# Sheet1.net
KiCad netlist of a schematic drawn in Altium Designer
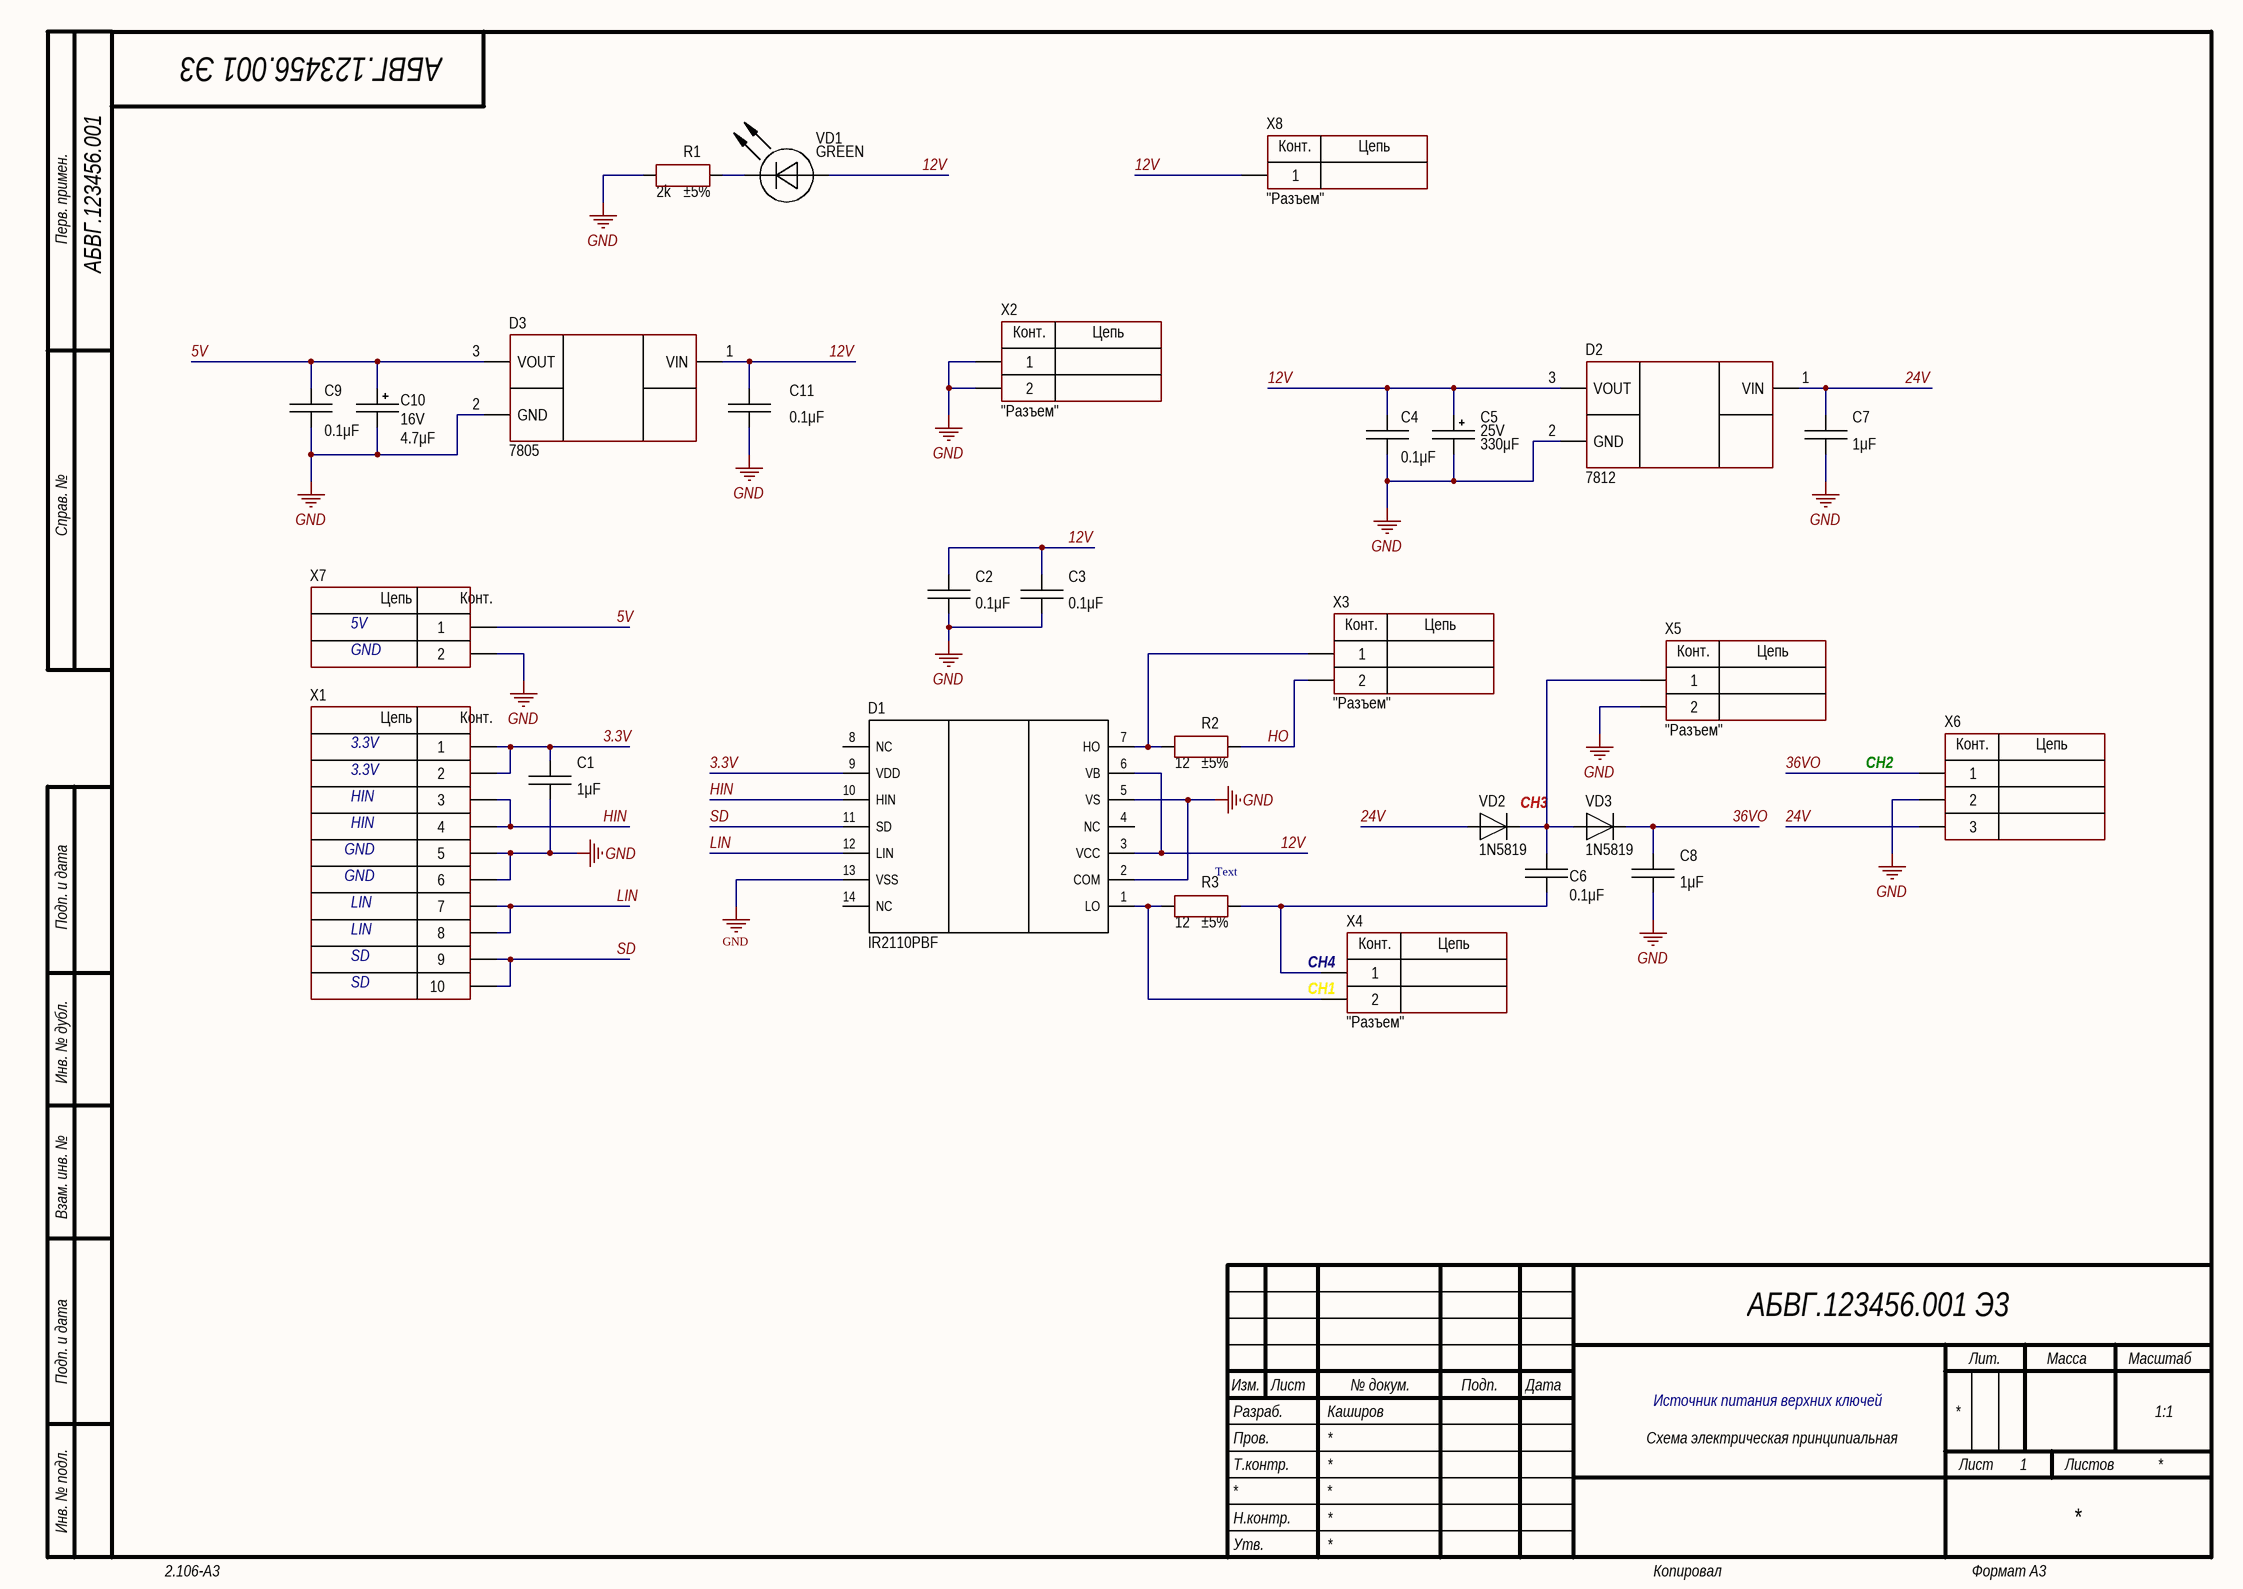
[diagram p0: Sheet1.SchDoc]

(export (version "E")
  (design (tool "Eeschema 10.0.6"))
  (components
    (comp (ref "C1") (value "1μF") (footprint "CAP: HOLE 5mm") (libsource (lib "capacitor") (part "Ceramic")))
    (comp (ref "C2")
      (value "0.1μF")
      (footprint "CAP: 0805")
      (fields
        (field (name "MANUFACTURER") "Yageo")
        (field (name "PARTNUMBER") "CC0805KRX7R7BB104")
        (field (name "VALUEMANUFACTURERPARTNUMBER") "Ceramic capacitor, 0.1μF, X7R, ±10%, , 0805, -55...+125°C")
      )
      (libsource (lib "capacitor") (part "Ceramic_0805"))
    )
    (comp (ref "C3")
      (value "0.1μF")
      (footprint "CAP: 0805")
      (fields
        (field (name "MANUFACTURER") "Yageo")
        (field (name "PARTNUMBER") "CC0805KRX7R7BB104")
        (field (name "VALUEMANUFACTURERPARTNUMBER") "Ceramic capacitor, 0.1μF, X7R, ±10%, , 0805, -55...+125°C")
      )
      (libsource (lib "capacitor") (part "Ceramic_0805"))
    )
    (comp (ref "C4")
      (value "0.1μF")
      (footprint "CAP: HOLE 5mm")
      (libsource (lib "capacitor") (part "Ceramic"))
    )
    (comp (ref "C5")
      (value "330μF")
      (footprint "CAP: D6.3C2.5H11")
      (fields
        (field (name "MANUFACTURER") "Wurth")
        (field (name "PARTNUMBER") "860080475013")
        (field (name "VALUEMANUFACTURERPARTNUMBER") "Aluminium capacitor, 330μF, 25V, ±20%, 54mOhm, 14x10x5 mm, -55...+105°C")
        (field (name "VOLTAGE") "25V")
      )
      (libsource (lib "capacitor") (part "Aluminium"))
    )
    (comp (ref "C6")
      (value "0.1μF")
      (footprint "CAP: HOLE 5mm")
      (libsource (lib "capacitor") (part "Ceramic"))
    )
    (comp (ref "C7") (value "1μF") (footprint "CAP: HOLE 5mm") (libsource (lib "capacitor") (part "Ceramic")))
    (comp (ref "C8") (value "1μF") (footprint "CAP: HOLE 5mm") (libsource (lib "capacitor") (part "Ceramic")))
    (comp (ref "C9")
      (value "0.1μF")
      (footprint "CAP: HOLE 5mm")
      (libsource (lib "capacitor") (part "Ceramic"))
    )
    (comp (ref "C10")
      (value "4.7μF")
      (footprint "CAP: TANTAL-A")
      (fields
        (field (name "MANUFACTURER") "AVX")
        (field (name "PARTNUMBER") "F930J107KAAAJ6")
        (field (name "VALUEMANUFACTURERPARTNUMBER") "Tantalum capacitor, 4.7μF, 16V, ±10%, 2Ohm, case A (3216), -55...+125°C")
        (field (name "VOLTAGE") "16V")
      )
      (libsource (lib "capacitor") (part "Tantal_A"))
    )
    (comp (ref "C11")
      (value "0.1μF")
      (footprint "CAP: 0805")
      (fields
        (field (name "MANUFACTURER") "Yageo")
        (field (name "PARTNUMBER") "CC0805KRX7R7BB104")
        (field (name "VALUEMANUFACTURERPARTNUMBER") "Ceramic capacitor, 0.1μF, X7R, ±10%, , 0805, -55...+125°C")
      )
      (libsource (lib "capacitor") (part "Ceramic_0805"))
    )
    (comp (ref "D1")
      (value "Infineon Technologies")
      (footprint "14-DIP")
      (description "Gate driver")
      (fields (field (name "PARTNUMBER") "IR2110PBF"))
      (libsource (lib "ic-gate-driver") (part "IR2110PBF"))
    )
    (comp (ref "D2")
      (value "*")
      (footprint "TO-220F")
      (description "Linear voltage regulator")
      (fields (field (name "PARTNUMBER") "7812"))
      (libsource (lib "ic-power-supply") (part "78XX"))
    )
    (comp (ref "D3")
      (value "*")
      (footprint "TO-220F")
      (description "Linear voltage regulator")
      (fields (field (name "PARTNUMBER") "7805"))
      (libsource (lib "ic-power-supply") (part "78XX"))
    )
    (comp (ref "R1")
      (value "2k")
      (footprint "RES: Axial 10mm")
      (fields (field (name "TOLERANCE") "±5%"))
      (libsource (lib "resistor") (part "Resistor_Axial"))
    )
    (comp (ref "R2")
      (value "12")
      (footprint "RES: Axial 10mm")
      (fields (field (name "TOLERANCE") "±5%"))
      (libsource (lib "resistor") (part "Resistor_Axial"))
    )
    (comp (ref "R3")
      (value "12")
      (footprint "RES: Axial 10mm")
      (fields (field (name "TOLERANCE") "±5%"))
      (libsource (lib "resistor") (part "Resistor_Axial"))
    )
    (comp (ref "VD1")
      (value "~")
      (footprint "LED: Axial 3MM")
      (fields
        (field (name "VALUEMANUFACTURERPARTNUMBER") "LED, Green, *, *, *, -55...+150°C")
        (field (name "COLOR") "GREEN")
      )
      (libsource (lib "diode") (part "LED_single"))
    )
    (comp (ref "VD2")
      (value "~")
      (footprint "DIODE: DO41")
      (fields
        (field (name "MANUFACTURER") "STMicroelectronics")
        (field (name "VALUEMANUFACTURERPARTNUMBER") "Single diode, 40V, 1A, 550mV, , DO-41, 150°C (Max)")
        (field (name "VOLTAGE") "40V")
        (field (name "PARTNUMBER") "1N5819")
      )
      (libsource (lib "diode") (part "Diode_single"))
    )
    (comp (ref "VD3")
      (value "~")
      (footprint "DIODE: DO41")
      (fields
        (field (name "MANUFACTURER") "STMicroelectronics")
        (field (name "VALUEMANUFACTURERPARTNUMBER") "Single diode, 40V, 1A, 550mV, , DO-41, 150°C (Max)")
        (field (name "VOLTAGE") "40V")
        (field (name "PARTNUMBER") "1N5819")
      )
      (libsource (lib "diode") (part "Diode_single"))
    )
    (comp (ref "X1")
      (value "~")
      (footprint "CON: PLD-10")
      (fields
        (field (name "MANUFACTURER") "Connfly")
        (field (name "VALUEMANUFACTURERPARTNUMBER") "Connector, 10pin, 2.54mm, 500VAC, 3A")
        (field (name "PARTNUMBER") "PLD-10")
      )
      (libsource (lib "connector") (part "PLD-10"))
    )
    (comp (ref "X2")
      (value "~")
      (footprint "CON: PLS-2")
      (fields
        (field (name "MANUFACTURER") "Connfly")
        (field (name "VALUEMANUFACTURERPARTNUMBER") "Connector, 2pin, 2.54mm, 500VAC, 3A")
        (field (name "PARTNUMBER") "PLS-2")
        (field (name "COMMENTTEXT") "\"Разъем\"")
      )
      (libsource (lib "") (part "PLS-2_1"))
    )
    (comp (ref "X3")
      (value "~")
      (footprint "CON: PLS-2")
      (fields
        (field (name "MANUFACTURER") "Connfly")
        (field (name "VALUEMANUFACTURERPARTNUMBER") "Connector, 2pin, 2.54mm, 500VAC, 3A")
        (field (name "PARTNUMBER") "PLS-2")
        (field (name "COMMENTTEXT") "\"Разъем\"")
      )
      (libsource (lib "") (part "PLS-2_1"))
    )
    (comp (ref "X4")
      (value "~")
      (footprint "CON: PLS-2")
      (fields
        (field (name "MANUFACTURER") "Connfly")
        (field (name "VALUEMANUFACTURERPARTNUMBER") "Connector, 2pin, 2.54mm, 500VAC, 3A")
        (field (name "PARTNUMBER") "PLS-2")
        (field (name "COMMENTTEXT") "\"Разъем\"")
      )
      (libsource (lib "") (part "PLS-2_1"))
    )
    (comp (ref "X5")
      (value "~")
      (footprint "CON: PLS-2")
      (fields
        (field (name "MANUFACTURER") "Connfly")
        (field (name "VALUEMANUFACTURERPARTNUMBER") "Connector, 2pin, 2.54mm, 500VAC, 3A")
        (field (name "PARTNUMBER") "PLS-2")
        (field (name "COMMENTTEXT") "\"Разъем\"")
      )
      (libsource (lib "") (part "PLS-2_1"))
    )
    (comp (ref "X6")
      (value "*")
      (footprint "CON: Terminal 3p 5mm")
      (libsource (lib "connector") (part "Terminal block 3"))
    )
    (comp (ref "X7")
      (value "~")
      (footprint "CON: PLS-2")
      (fields
        (field (name "MANUFACTURER") "Connfly")
        (field (name "VALUEMANUFACTURERPARTNUMBER") "Connector, 2pin, 2.54mm, 500VAC, 3A")
        (field (name "PARTNUMBER") "PLS-2")
      )
      (libsource (lib "connector") (part "PLS-2"))
    )
    (comp (ref "X8")
      (value "~")
      (footprint "CON: PLS-1")
      (fields
        (field (name "MANUFACTURER") "Connfly")
        (field (name "VALUEMANUFACTURERPARTNUMBER") "Connector, 1pin, 2.54mm, 500VAC, 3A")
        (field (name "PARTNUMBER") "PLS-1")
        (field (name "COMMENTTEXT") "\"Разъем\"")
      )
      (libsource (lib "connector") (part "PLS-1"))
    )
  )
  (nets
    (net (code "1") (name "/3.3V") (class "Default")
      (node (ref "C1") (pin "2") (pinfunction "2_2") (pintype "passive"))
      (node (ref "D1") (pin "9") (pinfunction "VDD_9") (pintype "passive"))
      (node (ref "X1") (pin "1") (pinfunction "1_1") (pintype "passive"))
      (node (ref "X1") (pin "2") (pinfunction "2_2") (pintype "passive"))
    )
    (net (code "2") (name "/5V") (class "Default")
      (node (ref "C10") (pin "1") (pinfunction "1_1") (pintype "passive"))
      (node (ref "C9") (pin "2") (pinfunction "2_2") (pintype "passive"))
      (node (ref "D3") (pin "3") (pinfunction "VOUT_3") (pintype "passive"))
      (node (ref "X7") (pin "1") (pinfunction "1_1") (pintype "passive"))
    )
    (net (code "3") (name "/12V") (class "Default")
      (node (ref "C11") (pin "2") (pinfunction "2_2") (pintype "passive"))
      (node (ref "C2") (pin "2") (pinfunction "2_2") (pintype "passive"))
      (node (ref "C3") (pin "2") (pinfunction "2_2") (pintype "passive"))
      (node (ref "C4") (pin "2") (pinfunction "2_2") (pintype "passive"))
      (node (ref "C5") (pin "1") (pinfunction "1_1") (pintype "passive"))
      (node (ref "D1") (pin "3") (pinfunction "VCC_3") (pintype "passive"))
      (node (ref "D1") (pin "6") (pinfunction "VB_6") (pintype "passive"))
      (node (ref "D2") (pin "3") (pinfunction "VOUT_3") (pintype "passive"))
      (node (ref "D3") (pin "1") (pinfunction "VIN_1") (pintype "passive"))
      (node (ref "VD1") (pin "1") (pinfunction "A_1") (pintype "passive"))
      (node (ref "X8") (pin "1") (pinfunction "1_1") (pintype "passive"))
    )
    (net (code "4") (name "/24V") (class "Default")
      (node (ref "C7") (pin "2") (pinfunction "2_2") (pintype "passive"))
      (node (ref "D2") (pin "1") (pinfunction "VIN_1") (pintype "passive"))
      (node (ref "VD2") (pin "1") (pinfunction "1_1") (pintype "passive"))
      (node (ref "X6") (pin "3") (pinfunction "3_3") (pintype "power_in"))
    )
    (net (code "5") (name "/36VO") (class "Default")
      (node (ref "C8") (pin "2") (pinfunction "2_2") (pintype "passive"))
      (node (ref "VD3") (pin "2") (pinfunction "2_2") (pintype "passive"))
      (node (ref "X6") (pin "1") (pinfunction "1_1") (pintype "passive"))
    )
    (net (code "6") (name "/HIN") (class "Default")
      (node (ref "D1") (pin "10") (pinfunction "HIN_10") (pintype "passive"))
      (node (ref "X1") (pin "3") (pinfunction "3_3") (pintype "power_in"))
      (node (ref "X1") (pin "4") (pinfunction "4_4") (pintype "power_in"))
    )
    (net (code "7") (name "/HO") (class "Default")
      (node (ref "R2") (pin "2") (pinfunction "2_2") (pintype "passive"))
      (node (ref "X3") (pin "2") (pinfunction "2_2") (pintype "passive"))
    )
    (net (code "8") (name "/LIN") (class "Default")
      (node (ref "D1") (pin "12") (pinfunction "LIN_12") (pintype "passive"))
      (node (ref "X1") (pin "7") (pinfunction "7_7") (pintype "power_in"))
      (node (ref "X1") (pin "8") (pinfunction "8_8") (pintype "power_in"))
    )
    (net (code "9") (name "/SD") (class "Default")
      (node (ref "D1") (pin "11") (pinfunction "SD_11") (pintype "passive"))
      (node (ref "X1") (pin "10") (pinfunction "10_10") (pintype "power_in"))
      (node (ref "X1") (pin "9") (pinfunction "9_9") (pintype "power_in"))
    )
    (net (code "10") (name "GND") (class "Default")
      (node (ref "C1") (pin "1") (pinfunction "1_1") (pintype "passive"))
      (node (ref "C10") (pin "2") (pinfunction "2_2") (pintype "passive"))
      (node (ref "C11") (pin "1") (pinfunction "1_1") (pintype "passive"))
      (node (ref "C2") (pin "1") (pinfunction "1_1") (pintype "passive"))
      (node (ref "C3") (pin "1") (pinfunction "1_1") (pintype "passive"))
      (node (ref "C4") (pin "1") (pinfunction "1_1") (pintype "passive"))
      (node (ref "C5") (pin "2") (pinfunction "2_2") (pintype "passive"))
      (node (ref "C7") (pin "1") (pinfunction "1_1") (pintype "passive"))
      (node (ref "C8") (pin "1") (pinfunction "1_1") (pintype "passive"))
      (node (ref "C9") (pin "1") (pinfunction "1_1") (pintype "passive"))
      (node (ref "D1") (pin "13") (pinfunction "VSS_13") (pintype "passive"))
      (node (ref "D1") (pin "2") (pinfunction "COM_2") (pintype "passive"))
      (node (ref "D1") (pin "5") (pinfunction "VS_5") (pintype "passive"))
      (node (ref "D2") (pin "2") (pinfunction "GND_2") (pintype "passive"))
      (node (ref "D3") (pin "2") (pinfunction "GND_2") (pintype "passive"))
      (node (ref "R1") (pin "1") (pinfunction "1_1") (pintype "passive"))
      (node (ref "X1") (pin "5") (pinfunction "5_5") (pintype "power_in"))
      (node (ref "X1") (pin "6") (pinfunction "6_6") (pintype "power_in"))
      (node (ref "X2") (pin "1") (pinfunction "1_1") (pintype "passive"))
      (node (ref "X2") (pin "2") (pinfunction "2_2") (pintype "passive"))
      (node (ref "X5") (pin "2") (pinfunction "2_2") (pintype "passive"))
      (node (ref "X6") (pin "2") (pinfunction "2_2") (pintype "passive"))
      (node (ref "X7") (pin "2") (pinfunction "2_2") (pintype "passive"))
    )
    (net (code "11") (name "Net-(C6-Pad1)") (class "Default")
      (node (ref "C6") (pin "1") (pinfunction "1_1") (pintype "passive"))
      (node (ref "VD2") (pin "2") (pinfunction "2_2") (pintype "passive"))
      (node (ref "VD3") (pin "1") (pinfunction "1_1") (pintype "passive"))
      (node (ref "X5") (pin "1") (pinfunction "1_1") (pintype "passive"))
    )
    (net (code "12") (name "Net-(C6-Pad2)") (class "Default")
      (node (ref "C6") (pin "2") (pinfunction "2_2") (pintype "passive"))
      (node (ref "R3") (pin "2") (pinfunction "2_2") (pintype "passive"))
      (node (ref "X4") (pin "1") (pinfunction "1_1") (pintype "passive"))
    )
    (net (code "13") (name "Net-(D1-HO)") (class "Default")
      (node (ref "D1") (pin "7") (pinfunction "HO_7") (pintype "passive"))
      (node (ref "R2") (pin "1") (pinfunction "1_1") (pintype "passive"))
      (node (ref "X3") (pin "1") (pinfunction "1_1") (pintype "passive"))
    )
    (net (code "14") (name "Net-(D1-LO)") (class "Default")
      (node (ref "D1") (pin "1") (pinfunction "LO_1") (pintype "passive"))
      (node (ref "R3") (pin "1") (pinfunction "1_1") (pintype "passive"))
      (node (ref "X4") (pin "2") (pinfunction "2_2") (pintype "passive"))
    )
    (net (code "15") (name "Net-(VD1-C)") (class "Default")
      (node (ref "R1") (pin "2") (pinfunction "2_2") (pintype "passive"))
      (node (ref "VD1") (pin "2") (pinfunction "C_2") (pintype "passive"))
    )
    (net (code "16") (name "unconnected-(D1-NC-Pad4)") (class "Default")
      (node (ref "D1") (pin "4") (pinfunction "NC_4") (pintype "passive"))
    )
    (net (code "17") (name "unconnected-(D1-NC-Pad8)") (class "Default")
      (node (ref "D1") (pin "8") (pinfunction "NC_8") (pintype "passive"))
    )
    (net (code "18") (name "unconnected-(D1-NC-Pad14)") (class "Default")
      (node (ref "D1") (pin "14") (pinfunction "NC_14") (pintype "passive"))
    )
  )
)
